# hexbot_bluetooth.net
KiCad netlist of a schematic drawn in Altium Designer
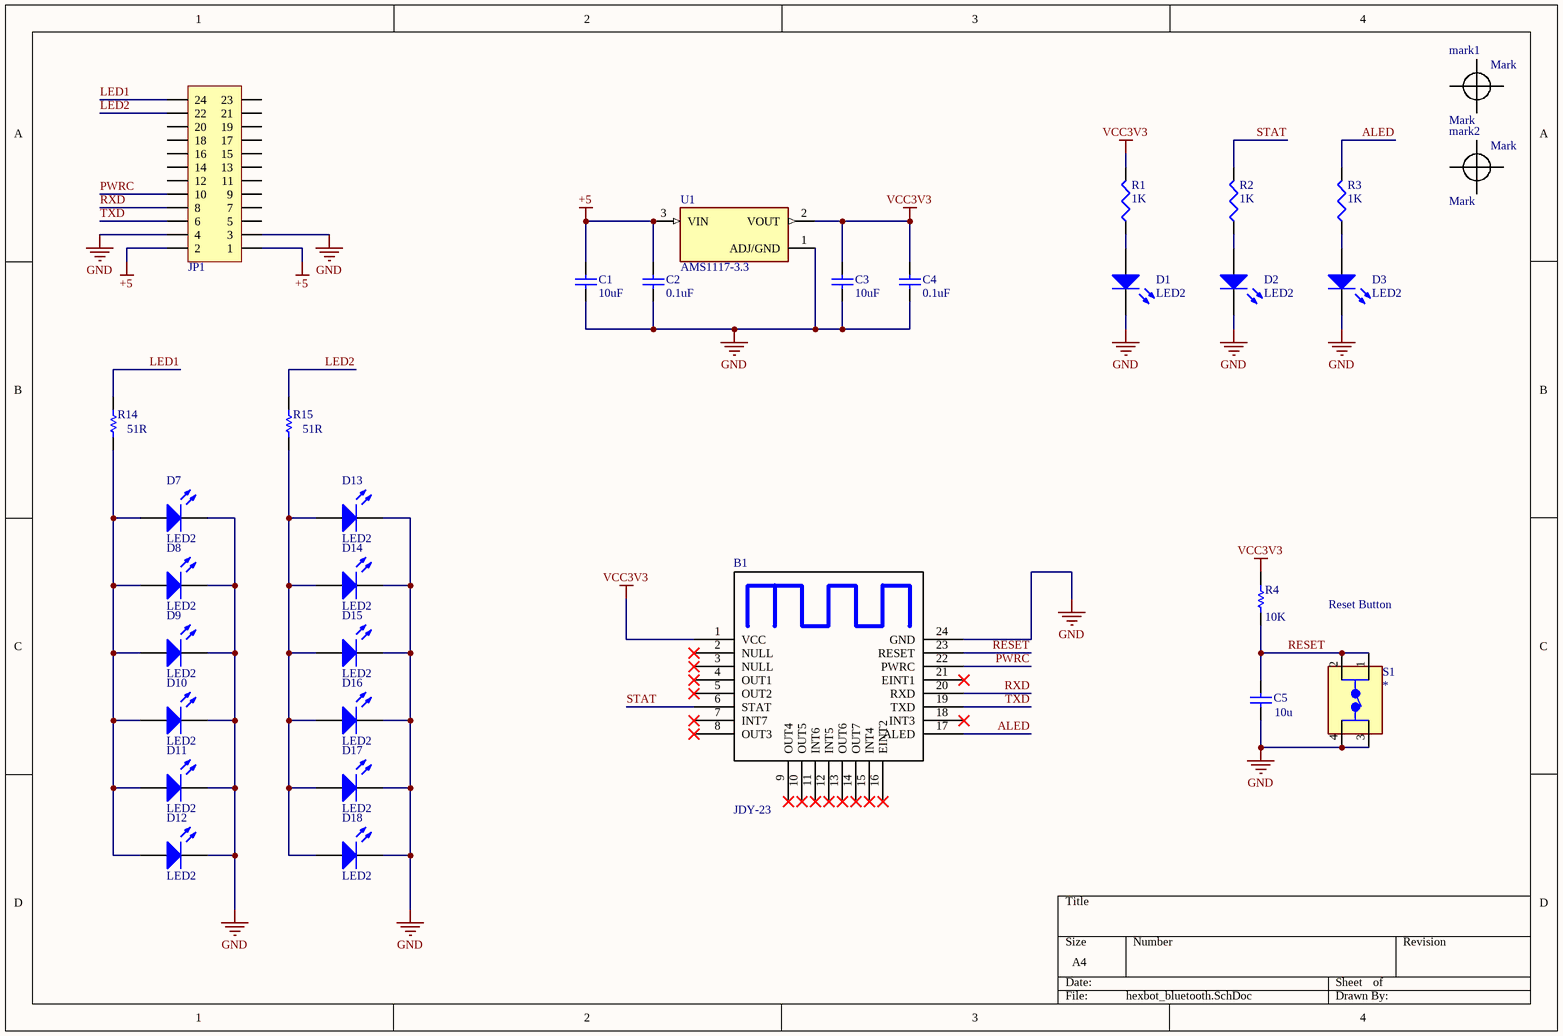
[diagram p0: hexbot_bluetooth.SchDoc]

(export (version "E")
  (design (tool "Eeschema 10.0.6"))
  (components
    (comp (ref "B1")
      (value "JDY-23")
      (footprint "BlueTooth_JDY-23")
      (libsource (lib "bluetooth") (part "BlueTooth"))
    )
    (comp (ref "C1")
      (value "10uF")
      (footprint "1608[0603]")
      (description "Capacitor (Semiconductor SIM Model)")
      (fields (field (name "PUBLISHER") "Altium Limited"))
      (libsource (lib "Miscellaneous Devices") (part "Cap Semi"))
    )
    (comp (ref "C2")
      (value "0.1uF")
      (footprint "1608[0603]")
      (description "Capacitor (Semiconductor SIM Model)")
      (fields (field (name "PUBLISHER") "Altium Limited"))
      (libsource (lib "Miscellaneous Devices") (part "Cap Semi"))
    )
    (comp (ref "C3")
      (value "10uF")
      (footprint "1608[0603]")
      (description "Capacitor (Semiconductor SIM Model)")
      (fields (field (name "PUBLISHER") "Altium Limited"))
      (libsource (lib "Miscellaneous Devices") (part "Cap Semi"))
    )
    (comp (ref "C4")
      (value "0.1uF")
      (footprint "1608[0603]")
      (description "Capacitor (Semiconductor SIM Model)")
      (fields (field (name "PUBLISHER") "Altium Limited"))
      (libsource (lib "Miscellaneous Devices") (part "Cap Semi"))
    )
    (comp (ref "C5")
      (value "10u")
      (footprint "1608[0603]")
      (description "Capacitor (Semiconductor SIM Model)")
      (fields (field (name "Comment") "Cap Semi") (field (name "PUBLISHER") "Altium Limited"))
      (libsource (lib "Miscellaneous Devices") (part "Cap Semi"))
    )
    (comp (ref "D1")
      (value "LED2")
      (footprint "DIOC1005X06N")
      (description "Typical RED, GREEN, YELLOW, AMBER GaAs LED")
      (fields (field (name "PUBLISHER") "Altium Limited"))
      (libsource (lib "Miscellaneous Devices") (part "LED2"))
    )
    (comp (ref "D2")
      (value "LED2")
      (footprint "DIOC1005X06N")
      (description "Typical RED, GREEN, YELLOW, AMBER GaAs LED")
      (fields (field (name "PUBLISHER") "Altium Limited"))
      (libsource (lib "Miscellaneous Devices") (part "LED2"))
    )
    (comp (ref "D3")
      (value "LED2")
      (footprint "DIOC1005X06N")
      (description "Typical RED, GREEN, YELLOW, AMBER GaAs LED")
      (fields (field (name "PUBLISHER") "Altium Limited"))
      (libsource (lib "Miscellaneous Devices") (part "LED2"))
    )
    (comp (ref "D7")
      (value "LED2")
      (footprint "DIOC1005X06N")
      (description "Typical RED, GREEN, YELLOW, AMBER GaAs LED")
      (fields (field (name "PUBLISHER") "Altium Limited"))
      (libsource (lib "Miscellaneous Devices") (part "LED2"))
    )
    (comp (ref "D8")
      (value "LED2")
      (footprint "DIOC1005X06N")
      (description "Typical RED, GREEN, YELLOW, AMBER GaAs LED")
      (fields (field (name "PUBLISHER") "Altium Limited"))
      (libsource (lib "Miscellaneous Devices") (part "LED2"))
    )
    (comp (ref "D9")
      (value "LED2")
      (footprint "DIOC1005X06N")
      (description "Typical RED, GREEN, YELLOW, AMBER GaAs LED")
      (fields (field (name "PUBLISHER") "Altium Limited"))
      (libsource (lib "Miscellaneous Devices") (part "LED2"))
    )
    (comp (ref "D10")
      (value "LED2")
      (footprint "DIOC1005X06N")
      (description "Typical RED, GREEN, YELLOW, AMBER GaAs LED")
      (fields (field (name "PUBLISHER") "Altium Limited"))
      (libsource (lib "Miscellaneous Devices") (part "LED2"))
    )
    (comp (ref "D11")
      (value "LED2")
      (footprint "DIOC1005X06N")
      (description "Typical RED, GREEN, YELLOW, AMBER GaAs LED")
      (fields (field (name "PUBLISHER") "Altium Limited"))
      (libsource (lib "Miscellaneous Devices") (part "LED2"))
    )
    (comp (ref "D12")
      (value "LED2")
      (footprint "DIOC1005X06N")
      (description "Typical RED, GREEN, YELLOW, AMBER GaAs LED")
      (fields (field (name "PUBLISHER") "Altium Limited"))
      (libsource (lib "Miscellaneous Devices") (part "LED2"))
    )
    (comp (ref "D13")
      (value "LED2")
      (footprint "DIOC1005X06N")
      (description "Typical RED, GREEN, YELLOW, AMBER GaAs LED")
      (fields (field (name "PUBLISHER") "Altium Limited"))
      (libsource (lib "Miscellaneous Devices") (part "LED2"))
    )
    (comp (ref "D14")
      (value "LED2")
      (footprint "DIOC1005X06N")
      (description "Typical RED, GREEN, YELLOW, AMBER GaAs LED")
      (fields (field (name "PUBLISHER") "Altium Limited"))
      (libsource (lib "Miscellaneous Devices") (part "LED2"))
    )
    (comp (ref "D15")
      (value "LED2")
      (footprint "DIOC1005X06N")
      (description "Typical RED, GREEN, YELLOW, AMBER GaAs LED")
      (fields (field (name "PUBLISHER") "Altium Limited"))
      (libsource (lib "Miscellaneous Devices") (part "LED2"))
    )
    (comp (ref "D16")
      (value "LED2")
      (footprint "DIOC1005X06N")
      (description "Typical RED, GREEN, YELLOW, AMBER GaAs LED")
      (fields (field (name "PUBLISHER") "Altium Limited"))
      (libsource (lib "Miscellaneous Devices") (part "LED2"))
    )
    (comp (ref "D17")
      (value "LED2")
      (footprint "DIOC1005X06N")
      (description "Typical RED, GREEN, YELLOW, AMBER GaAs LED")
      (fields (field (name "PUBLISHER") "Altium Limited"))
      (libsource (lib "Miscellaneous Devices") (part "LED2"))
    )
    (comp (ref "D18")
      (value "LED2")
      (footprint "DIOC1005X06N")
      (description "Typical RED, GREEN, YELLOW, AMBER GaAs LED")
      (fields (field (name "PUBLISHER") "Altium Limited"))
      (libsource (lib "Miscellaneous Devices") (part "LED2"))
    )
    (comp (ref "JP1")
      (value "Header 2X11")
      (footprint "HDR2.54-WI-2x12P")
      (description "12*2P接插件")
      (fields (field (name "版权归属") "封装库来自淘宝卖家 ID：黄晶宝石"))
      (libsource (lib "5.4 - 接插件-脚距2.54 (100mil) ") (part "Header 12X2"))
    )
    (comp (ref "mark1") (value "Mark") (footprint "Mark:Mark") (libsource (lib "Mark") (part "Mark")))
    (comp (ref "mark2") (value "Mark") (footprint "Mark:Mark") (libsource (lib "Mark") (part "Mark")))
    (comp (ref "R1")
      (value "1K")
      (footprint "1608[0603]")
      (description "Resistor")
      (fields (field (name "PUBLISHER") "Altium Limited"))
      (libsource (lib "Miscellaneous Devices") (part "Res3"))
    )
    (comp (ref "R2")
      (value "1K")
      (footprint "1608[0603]")
      (description "Resistor")
      (fields (field (name "PUBLISHER") "Altium Limited"))
      (libsource (lib "Miscellaneous Devices") (part "Res3"))
    )
    (comp (ref "R3")
      (value "1K")
      (footprint "1608[0603]")
      (description "Resistor")
      (fields (field (name "PUBLISHER") "Altium Limited"))
      (libsource (lib "Miscellaneous Devices") (part "Res3"))
    )
    (comp (ref "R4")
      (value "10K")
      (footprint "1608[0603]")
      (description "Resistor")
      (fields (field (name "Comment") "Res1") (field (name "PUBLISHER") "Altium Limited"))
      (libsource (lib "Miscellaneous Devices") (part "Res1"))
    )
    (comp (ref "R14")
      (value "51R")
      (footprint "1608[0603]")
      (description "Resistor")
      (fields (field (name "PUBLISHER") "Altium Limited"))
      (libsource (lib "hexbot_main") (part "Res1"))
    )
    (comp (ref "R15")
      (value "51R")
      (footprint "1608[0603]")
      (description "Resistor")
      (fields (field (name "PUBLISHER") "Altium Limited"))
      (libsource (lib "hexbot_main") (part "Res1"))
    )
    (comp (ref "S1")
      (value "4-1437565-1")
      (footprint "TE_FSM4JSMA")
      (description "Tactile Switch SPST-NO Top Actuated Surface Mount")
      (fields
        (field (name "MP") "FSM4JSMA")
        (field (name "MF") "TE Connectivity")
        (field (name "COMMENT_1") "*")
      )
      (libsource (lib "FSM4JSMA") (part "FSM4JSMA"))
    )
    (comp (ref "U1")
      (value "AMS1117-3.3")
      (footprint "SOT-223-4_L6.5-W3.5-P2.30-LS7.0-BR")
      (description "Sot223/Pkg 1-Amp 3.3-Volt Low Drop Out Voltage Regulatator")
      (fields (field (name "MF") "Advanced Monolithic Systems"))
      (libsource (lib "AMS1117 - 3.3") (part "AMS1117-3.3"))
    )
  )
  (nets
    (net (code "1") (name "+5") (class "Default")
      (node (ref "C1") (pin "2") (pinfunction "2_2") (pintype "passive"))
      (node (ref "C2") (pin "2") (pinfunction "2_2") (pintype "passive"))
      (node (ref "JP1") (pin "1") (pinfunction "1_1") (pintype "passive"))
      (node (ref "JP1") (pin "2") (pinfunction "2_2") (pintype "passive"))
      (node (ref "U1") (pin "3") (pinfunction "VIN_3") (pintype "input"))
    )
    (net (code "2") (name "/ALED") (class "Default")
      (node (ref "B1") (pin "17") (pinfunction "ALED_17") (pintype "passive"))
      (node (ref "R3") (pin "2") (pinfunction "2_2") (pintype "passive"))
    )
    (net (code "3") (name "/LED1") (class "Default")
      (node (ref "JP1") (pin "24") (pinfunction "24_24") (pintype "passive"))
      (node (ref "R14") (pin "2") (pinfunction "2_2") (pintype "passive"))
    )
    (net (code "4") (name "/LED2") (class "Default")
      (node (ref "JP1") (pin "22") (pinfunction "22_22") (pintype "passive"))
      (node (ref "R15") (pin "2") (pinfunction "2_2") (pintype "passive"))
    )
    (net (code "5") (name "/PWRC") (class "Default")
      (node (ref "B1") (pin "22") (pinfunction "PWRC_22") (pintype "passive"))
      (node (ref "JP1") (pin "10") (pinfunction "10_10") (pintype "passive"))
    )
    (net (code "6") (name "/RESET") (class "Default")
      (node (ref "B1") (pin "23") (pinfunction "RESET_23") (pintype "passive"))
      (node (ref "C5") (pin "2") (pinfunction "2_2") (pintype "passive"))
      (node (ref "R4") (pin "1") (pinfunction "1_1") (pintype "passive"))
      (node (ref "S1") (pin "1") (pinfunction "1_1") (pintype "passive"))
      (node (ref "S1") (pin "2") (pinfunction "2_2") (pintype "passive"))
    )
    (net (code "7") (name "/RXD") (class "Default")
      (node (ref "B1") (pin "20") (pinfunction "RXD_20") (pintype "passive"))
      (node (ref "JP1") (pin "8") (pinfunction "8_8") (pintype "passive"))
    )
    (net (code "8") (name "/STAT") (class "Default")
      (node (ref "B1") (pin "6") (pinfunction "STAT_6") (pintype "passive"))
      (node (ref "R2") (pin "2") (pinfunction "2_2") (pintype "passive"))
    )
    (net (code "9") (name "/TXD") (class "Default")
      (node (ref "B1") (pin "19") (pinfunction "TXD_19") (pintype "passive"))
      (node (ref "JP1") (pin "6") (pinfunction "6_6") (pintype "passive"))
    )
    (net (code "10") (name "GND") (class "Default")
      (node (ref "B1") (pin "24") (pinfunction "GND_24") (pintype "passive"))
      (node (ref "C1") (pin "1") (pinfunction "1_1") (pintype "passive"))
      (node (ref "C2") (pin "1") (pinfunction "1_1") (pintype "passive"))
      (node (ref "C3") (pin "1") (pinfunction "1_1") (pintype "passive"))
      (node (ref "C4") (pin "1") (pinfunction "1_1") (pintype "passive"))
      (node (ref "C5") (pin "1") (pinfunction "1_1") (pintype "passive"))
      (node (ref "D1") (pin "2") (pinfunction "K_2") (pintype "passive"))
      (node (ref "D10") (pin "2") (pinfunction "K_2") (pintype "passive"))
      (node (ref "D11") (pin "2") (pinfunction "K_2") (pintype "passive"))
      (node (ref "D12") (pin "2") (pinfunction "K_2") (pintype "passive"))
      (node (ref "D13") (pin "2") (pinfunction "K_2") (pintype "passive"))
      (node (ref "D14") (pin "2") (pinfunction "K_2") (pintype "passive"))
      (node (ref "D15") (pin "2") (pinfunction "K_2") (pintype "passive"))
      (node (ref "D16") (pin "2") (pinfunction "K_2") (pintype "passive"))
      (node (ref "D17") (pin "2") (pinfunction "K_2") (pintype "passive"))
      (node (ref "D18") (pin "2") (pinfunction "K_2") (pintype "passive"))
      (node (ref "D2") (pin "2") (pinfunction "K_2") (pintype "passive"))
      (node (ref "D3") (pin "2") (pinfunction "K_2") (pintype "passive"))
      (node (ref "D7") (pin "2") (pinfunction "K_2") (pintype "passive"))
      (node (ref "D8") (pin "2") (pinfunction "K_2") (pintype "passive"))
      (node (ref "D9") (pin "2") (pinfunction "K_2") (pintype "passive"))
      (node (ref "JP1") (pin "3") (pinfunction "3_3") (pintype "passive"))
      (node (ref "JP1") (pin "4") (pinfunction "4_4") (pintype "passive"))
      (node (ref "S1") (pin "3") (pinfunction "3_3") (pintype "passive"))
      (node (ref "S1") (pin "4") (pinfunction "4_4") (pintype "passive"))
      (node (ref "U1") (pin "1") (pinfunction "ADJ/GND_1") (pintype "power_in"))
    )
    (net (code "11") (name "Net-(D1-A)") (class "Default")
      (node (ref "D1") (pin "1") (pinfunction "A_1") (pintype "passive"))
      (node (ref "R1") (pin "1") (pinfunction "1_1") (pintype "passive"))
    )
    (net (code "12") (name "Net-(D2-A)") (class "Default")
      (node (ref "D2") (pin "1") (pinfunction "A_1") (pintype "passive"))
      (node (ref "R2") (pin "1") (pinfunction "1_1") (pintype "passive"))
    )
    (net (code "13") (name "Net-(D3-A)") (class "Default")
      (node (ref "D3") (pin "1") (pinfunction "A_1") (pintype "passive"))
      (node (ref "R3") (pin "1") (pinfunction "1_1") (pintype "passive"))
    )
    (net (code "14") (name "Net-(D10-A)") (class "Default")
      (node (ref "D10") (pin "1") (pinfunction "A_1") (pintype "passive"))
      (node (ref "D11") (pin "1") (pinfunction "A_1") (pintype "passive"))
      (node (ref "D12") (pin "1") (pinfunction "A_1") (pintype "passive"))
      (node (ref "D7") (pin "1") (pinfunction "A_1") (pintype "passive"))
      (node (ref "D8") (pin "1") (pinfunction "A_1") (pintype "passive"))
      (node (ref "D9") (pin "1") (pinfunction "A_1") (pintype "passive"))
      (node (ref "R14") (pin "1") (pinfunction "1_1") (pintype "passive"))
    )
    (net (code "15") (name "Net-(D13-A)") (class "Default")
      (node (ref "D13") (pin "1") (pinfunction "A_1") (pintype "passive"))
      (node (ref "D14") (pin "1") (pinfunction "A_1") (pintype "passive"))
      (node (ref "D15") (pin "1") (pinfunction "A_1") (pintype "passive"))
      (node (ref "D16") (pin "1") (pinfunction "A_1") (pintype "passive"))
      (node (ref "D17") (pin "1") (pinfunction "A_1") (pintype "passive"))
      (node (ref "D18") (pin "1") (pinfunction "A_1") (pintype "passive"))
      (node (ref "R15") (pin "1") (pinfunction "1_1") (pintype "passive"))
    )
    (net (code "16") (name "VCC3V3") (class "Default")
      (node (ref "B1") (pin "1") (pinfunction "VCC_1") (pintype "passive"))
      (node (ref "C3") (pin "2") (pinfunction "2_2") (pintype "passive"))
      (node (ref "C4") (pin "2") (pinfunction "2_2") (pintype "passive"))
      (node (ref "R1") (pin "2") (pinfunction "2_2") (pintype "passive"))
      (node (ref "R4") (pin "2") (pinfunction "2_2") (pintype "passive"))
      (node (ref "U1") (pin "2") (pinfunction "VOUT_2") (pintype "output"))
    )
    (net (code "17") (name "unconnected-(B1-EINT1-Pad21)") (class "Default")
      (node (ref "B1") (pin "21") (pinfunction "EINT1_21") (pintype "passive+no_connect"))
    )
    (net (code "18") (name "unconnected-(B1-EINT2-Pad16)") (class "Default")
      (node (ref "B1") (pin "16") (pinfunction "EINT2_16") (pintype "passive+no_connect"))
    )
    (net (code "19") (name "unconnected-(B1-INT3-Pad18)") (class "Default")
      (node (ref "B1") (pin "18") (pinfunction "INT3_18") (pintype "passive+no_connect"))
    )
    (net (code "20") (name "unconnected-(B1-INT4-Pad15)") (class "Default")
      (node (ref "B1") (pin "15") (pinfunction "INT4_15") (pintype "passive+no_connect"))
    )
    (net (code "21") (name "unconnected-(B1-INT5-Pad12)") (class "Default")
      (node (ref "B1") (pin "12") (pinfunction "INT5_12") (pintype "passive+no_connect"))
    )
    (net (code "22") (name "unconnected-(B1-INT6-Pad11)") (class "Default")
      (node (ref "B1") (pin "11") (pinfunction "INT6_11") (pintype "passive+no_connect"))
    )
    (net (code "23") (name "unconnected-(B1-INT7-Pad7)") (class "Default")
      (node (ref "B1") (pin "7") (pinfunction "INT7_7") (pintype "passive+no_connect"))
    )
    (net (code "24") (name "unconnected-(B1-NULL-Pad2)") (class "Default")
      (node (ref "B1") (pin "2") (pinfunction "NULL_2") (pintype "passive+no_connect"))
    )
    (net (code "25") (name "unconnected-(B1-NULL-Pad3)") (class "Default")
      (node (ref "B1") (pin "3") (pinfunction "NULL_3") (pintype "passive+no_connect"))
    )
    (net (code "26") (name "unconnected-(B1-OUT1-Pad4)") (class "Default")
      (node (ref "B1") (pin "4") (pinfunction "OUT1_4") (pintype "passive+no_connect"))
    )
    (net (code "27") (name "unconnected-(B1-OUT2-Pad5)") (class "Default")
      (node (ref "B1") (pin "5") (pinfunction "OUT2_5") (pintype "passive+no_connect"))
    )
    (net (code "28") (name "unconnected-(B1-OUT3-Pad8)") (class "Default")
      (node (ref "B1") (pin "8") (pinfunction "OUT3_8") (pintype "passive+no_connect"))
    )
    (net (code "29") (name "unconnected-(B1-OUT4-Pad9)") (class "Default")
      (node (ref "B1") (pin "9") (pinfunction "OUT4_9") (pintype "passive+no_connect"))
    )
    (net (code "30") (name "unconnected-(B1-OUT5-Pad10)") (class "Default")
      (node (ref "B1") (pin "10") (pinfunction "OUT5_10") (pintype "passive+no_connect"))
    )
    (net (code "31") (name "unconnected-(B1-OUT6-Pad13)") (class "Default")
      (node (ref "B1") (pin "13") (pinfunction "OUT6_13") (pintype "passive+no_connect"))
    )
    (net (code "32") (name "unconnected-(B1-OUT7-Pad14)") (class "Default")
      (node (ref "B1") (pin "14") (pinfunction "OUT7_14") (pintype "passive+no_connect"))
    )
    (net (code "33") (name "unconnected-(JP1-Pad5)") (class "Default")
      (node (ref "JP1") (pin "5") (pinfunction "5_5") (pintype "passive"))
    )
    (net (code "34") (name "unconnected-(JP1-Pad7)") (class "Default")
      (node (ref "JP1") (pin "7") (pinfunction "7_7") (pintype "passive"))
    )
    (net (code "35") (name "unconnected-(JP1-Pad9)") (class "Default")
      (node (ref "JP1") (pin "9") (pinfunction "9_9") (pintype "passive"))
    )
    (net (code "36") (name "unconnected-(JP1-Pad11)") (class "Default")
      (node (ref "JP1") (pin "11") (pinfunction "11_11") (pintype "passive"))
    )
    (net (code "37") (name "unconnected-(JP1-Pad12)") (class "Default")
      (node (ref "JP1") (pin "12") (pinfunction "12_12") (pintype "passive"))
    )
    (net (code "38") (name "unconnected-(JP1-Pad13)") (class "Default")
      (node (ref "JP1") (pin "13") (pinfunction "13_13") (pintype "passive"))
    )
    (net (code "39") (name "unconnected-(JP1-Pad14)") (class "Default")
      (node (ref "JP1") (pin "14") (pinfunction "14_14") (pintype "passive"))
    )
    (net (code "40") (name "unconnected-(JP1-Pad15)") (class "Default")
      (node (ref "JP1") (pin "15") (pinfunction "15_15") (pintype "passive"))
    )
    (net (code "41") (name "unconnected-(JP1-Pad16)") (class "Default")
      (node (ref "JP1") (pin "16") (pinfunction "16_16") (pintype "passive"))
    )
    (net (code "42") (name "unconnected-(JP1-Pad17)") (class "Default")
      (node (ref "JP1") (pin "17") (pinfunction "17_17") (pintype "passive"))
    )
    (net (code "43") (name "unconnected-(JP1-Pad18)") (class "Default")
      (node (ref "JP1") (pin "18") (pinfunction "18_18") (pintype "passive"))
    )
    (net (code "44") (name "unconnected-(JP1-Pad19)") (class "Default")
      (node (ref "JP1") (pin "19") (pinfunction "19_19") (pintype "passive"))
    )
    (net (code "45") (name "unconnected-(JP1-Pad20)") (class "Default")
      (node (ref "JP1") (pin "20") (pinfunction "20_20") (pintype "passive"))
    )
    (net (code "46") (name "unconnected-(JP1-Pad21)") (class "Default")
      (node (ref "JP1") (pin "21") (pinfunction "21_21") (pintype "passive"))
    )
    (net (code "47") (name "unconnected-(JP1-Pad23)") (class "Default")
      (node (ref "JP1") (pin "23") (pinfunction "23_23") (pintype "passive"))
    )
  )
)
